# 2_Motors_V3.net
KiCad netlist of a schematic drawn in EAGLE
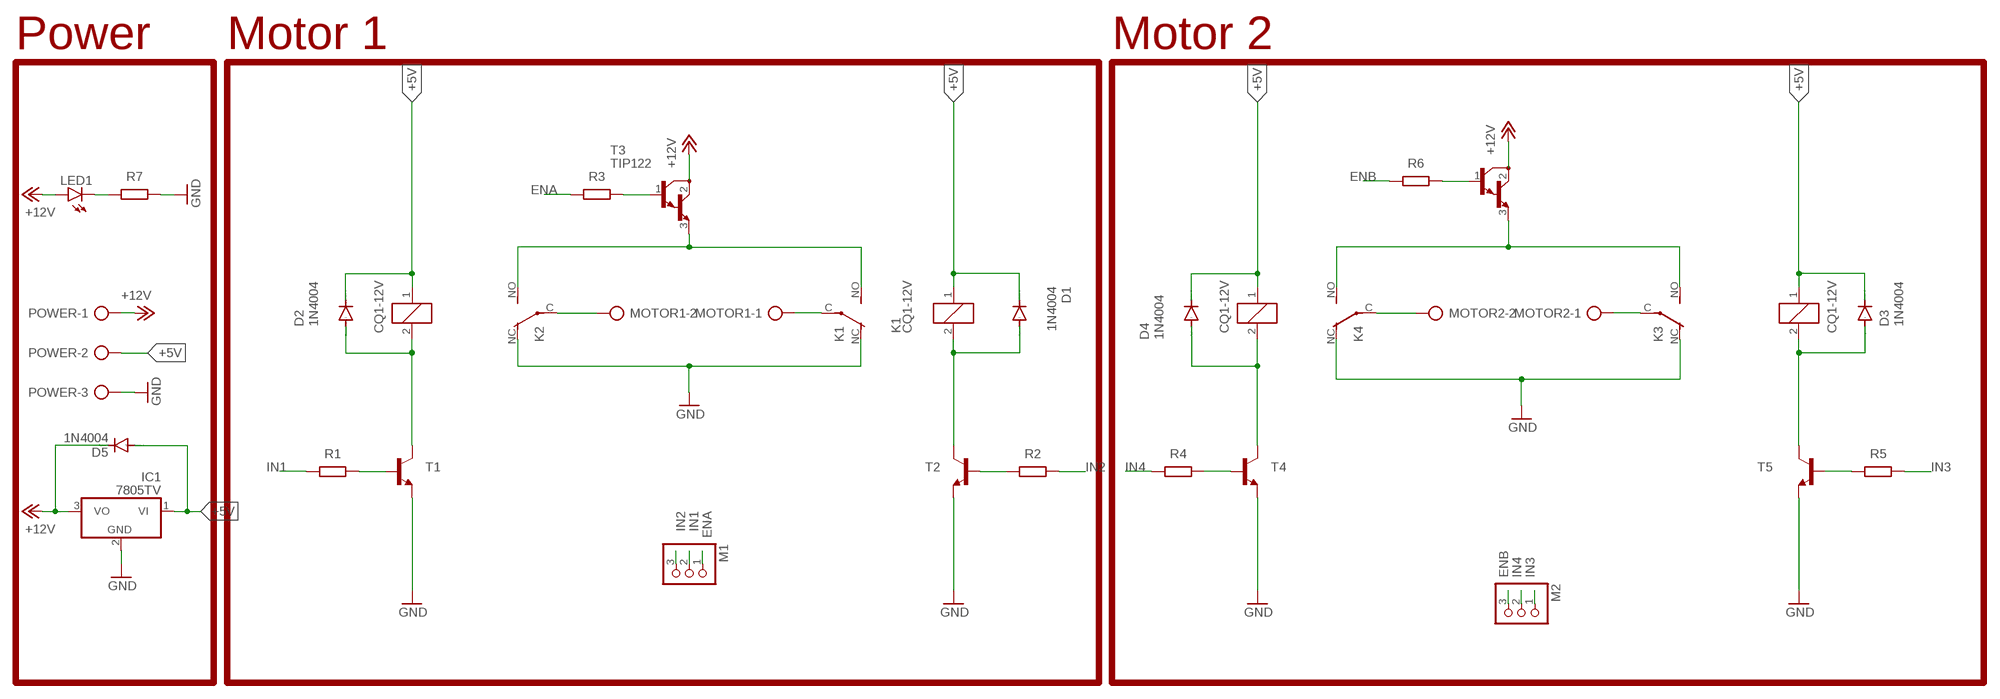
[diagram p0: schematic, sheet 1]

(export (version "E")
  (design (tool "Eeschema 10.0.6"))
  (components
    (comp (ref "D1")
      (value "1N4004")
      (footprint "eagle-import:DO41-10")
      (libsource (lib "eagle-import") (part "1N4004"))
    )
    (comp (ref "D2")
      (value "1N4004")
      (footprint "eagle-import:DO41-10")
      (libsource (lib "eagle-import") (part "1N4004"))
    )
    (comp (ref "D3")
      (value "1N4004")
      (footprint "eagle-import:DO41-10")
      (libsource (lib "eagle-import") (part "1N4004"))
    )
    (comp (ref "D4")
      (value "1N4004")
      (footprint "eagle-import:DO41-10")
      (libsource (lib "eagle-import") (part "1N4004"))
    )
    (comp (ref "D5")
      (value "1N4004")
      (footprint "eagle-import:DO41-10")
      (libsource (lib "eagle-import") (part "1N4004"))
    )
    (comp (ref "IC1")
      (value "7805TV")
      (footprint "eagle-import:TO220V")
      (libsource (lib "eagle-import") (part "78TV05"))
    )
    (comp (ref "K1")
      (value "CQ1-12V")
      (footprint "eagle-import:CQ1")
      (libsource (lib "eagle-import") (part "CQ1-12V"))
    )
    (comp (ref "K2")
      (value "CQ1-12V")
      (footprint "eagle-import:CQ1")
      (libsource (lib "eagle-import") (part "CQ1-12V"))
    )
    (comp (ref "K3")
      (value "CQ1-12V")
      (footprint "eagle-import:CQ1")
      (libsource (lib "eagle-import") (part "CQ1-12V"))
    )
    (comp (ref "K4")
      (value "CQ1-12V")
      (footprint "eagle-import:CQ1")
      (libsource (lib "eagle-import") (part "CQ1-12V"))
    )
    (comp (ref "LED1")
      (value "LED3MM")
      (footprint "eagle-import:LED3MM")
      (libsource (lib "eagle-import") (part "LED3MM"))
    )
    (comp (ref "M1")
      (value "PINHD-1X3")
      (footprint "eagle-import:1X03")
      (libsource (lib "eagle-import") (part "PINHD-1X3"))
    )
    (comp (ref "M2")
      (value "PINHD-1X3")
      (footprint "eagle-import:1X03")
      (libsource (lib "eagle-import") (part "PINHD-1X3"))
    )
    (comp (ref "MOTOR1")
      (value "AK300/2")
      (footprint "eagle-import:AK300_2")
      (libsource (lib "eagle-import") (part "AK300/2"))
    )
    (comp (ref "MOTOR2")
      (value "AK300/2")
      (footprint "eagle-import:AK300_2")
      (libsource (lib "eagle-import") (part "AK300/2"))
    )
    (comp (ref "POWER")
      (value "AK300/3")
      (footprint "eagle-import:AK300_3")
      (libsource (lib "eagle-import") (part "AK300/3"))
    )
    (comp (ref "R1")
      (value "4.7k")
      (footprint "eagle-import:0204_7")
      (libsource (lib "eagle-import") (part "R-EU_0204/7"))
    )
    (comp (ref "R2")
      (value "4.7k")
      (footprint "eagle-import:0204_7")
      (libsource (lib "eagle-import") (part "R-EU_0204/7"))
    )
    (comp (ref "R3")
      (value "4.7k")
      (footprint "eagle-import:0204_7")
      (libsource (lib "eagle-import") (part "R-EU_0204/7"))
    )
    (comp (ref "R4")
      (value "4.7k")
      (footprint "eagle-import:0204_7")
      (libsource (lib "eagle-import") (part "R-EU_0204/7"))
    )
    (comp (ref "R5")
      (value "4.7k")
      (footprint "eagle-import:0204_7")
      (libsource (lib "eagle-import") (part "R-EU_0204/7"))
    )
    (comp (ref "R6")
      (value "4.7k")
      (footprint "eagle-import:0204_7")
      (libsource (lib "eagle-import") (part "R-EU_0204/7"))
    )
    (comp (ref "R7")
      (value "330")
      (footprint "eagle-import:0204_7")
      (libsource (lib "eagle-import") (part "R-EU_0204/7"))
    )
    (comp (ref "T1")
      (value "2N2222-NPN-TO92-EBC")
      (footprint "eagle-import:TO92-EBC")
      (libsource (lib "eagle-import") (part "-NPN-TO92-EBC2N2222"))
    )
    (comp (ref "T2")
      (value "2N2222-NPN-TO92-EBC")
      (footprint "eagle-import:TO92-EBC")
      (libsource (lib "eagle-import") (part "-NPN-TO92-EBC2N2222"))
    )
    (comp (ref "T3")
      (value "TIP122")
      (footprint "eagle-import:TO220")
      (libsource (lib "eagle-import") (part "TIP122"))
    )
    (comp (ref "T4")
      (value "2N2222-NPN-TO92-EBC")
      (footprint "eagle-import:TO92-EBC")
      (libsource (lib "eagle-import") (part "-NPN-TO92-EBC2N2222"))
    )
    (comp (ref "T5")
      (value "2N2222-NPN-TO92-EBC")
      (footprint "eagle-import:TO92-EBC")
      (libsource (lib "eagle-import") (part "-NPN-TO92-EBC2N2222"))
    )
    (comp (ref "T6")
      (value "TIP122")
      (footprint "eagle-import:TO220")
      (libsource (lib "eagle-import") (part "TIP122"))
    )
  )
  (nets
    (net (code "1") (name "+5V") (class "Default")
      (node (ref "D1") (pin "C") (pinfunction "C_C") (pintype "passive"))
      (node (ref "D2") (pin "C") (pinfunction "C_C") (pintype "passive"))
      (node (ref "D3") (pin "C") (pinfunction "C_C") (pintype "passive"))
      (node (ref "D4") (pin "C") (pinfunction "C_C") (pintype "passive"))
      (node (ref "D5") (pin "A") (pinfunction "A_A") (pintype "passive"))
      (node (ref "IC1") (pin "1") (pinfunction "VI_1") (pintype "input"))
      (node (ref "K1") (pin "1") (pinfunction "1_1") (pintype "passive"))
      (node (ref "K2") (pin "1") (pinfunction "1_1") (pintype "passive"))
      (node (ref "K3") (pin "1") (pinfunction "1_1") (pintype "passive"))
      (node (ref "K4") (pin "1") (pinfunction "1_1") (pintype "passive"))
      (node (ref "POWER") (pin "2") (pinfunction "KL_2") (pintype "passive"))
    )
    (net (code "2") (name "+12V") (class "Default")
      (node (ref "D5") (pin "C") (pinfunction "C_C") (pintype "passive"))
      (node (ref "IC1") (pin "3") (pinfunction "VO_3") (pintype "passive"))
      (node (ref "LED1") (pin "A") (pinfunction "A_A") (pintype "passive"))
      (node (ref "POWER") (pin "1") (pinfunction "KL_1") (pintype "passive"))
      (node (ref "T3") (pin "2") (pinfunction "C_2") (pintype "passive"))
      (node (ref "T6") (pin "2") (pinfunction "C_2") (pintype "passive"))
    )
    (net (code "3") (name "/ENA") (class "Default")
      (node (ref "M1") (pin "1") (pinfunction "1_1") (pintype "passive"))
      (node (ref "R3") (pin "2") (pinfunction "2_2") (pintype "passive"))
    )
    (net (code "4") (name "/ENB") (class "Default")
      (node (ref "M2") (pin "3") (pinfunction "3_3") (pintype "passive"))
      (node (ref "R6") (pin "2") (pinfunction "2_2") (pintype "passive"))
    )
    (net (code "5") (name "/IN1") (class "Default")
      (node (ref "M1") (pin "2") (pinfunction "2_2") (pintype "passive"))
      (node (ref "R1") (pin "1") (pinfunction "1_1") (pintype "passive"))
    )
    (net (code "6") (name "/IN2") (class "Default")
      (node (ref "M1") (pin "3") (pinfunction "3_3") (pintype "passive"))
      (node (ref "R2") (pin "1") (pinfunction "1_1") (pintype "passive"))
    )
    (net (code "7") (name "/IN3") (class "Default")
      (node (ref "M2") (pin "1") (pinfunction "1_1") (pintype "passive"))
      (node (ref "R5") (pin "1") (pinfunction "1_1") (pintype "passive"))
    )
    (net (code "8") (name "/IN4") (class "Default")
      (node (ref "M2") (pin "2") (pinfunction "2_2") (pintype "passive"))
      (node (ref "R4") (pin "2") (pinfunction "2_2") (pintype "passive"))
    )
    (net (code "9") (name "GND") (class "Default")
      (node (ref "IC1") (pin "2") (pinfunction "GND_2") (pintype "passive"))
      (node (ref "K1") (pin "NC") (pinfunction "O_NC") (pintype "passive"))
      (node (ref "K2") (pin "NC") (pinfunction "O_NC") (pintype "passive"))
      (node (ref "K3") (pin "NC") (pinfunction "O_NC") (pintype "passive"))
      (node (ref "K4") (pin "NC") (pinfunction "O_NC") (pintype "passive"))
      (node (ref "POWER") (pin "3") (pinfunction "KL_3") (pintype "passive"))
      (node (ref "R7") (pin "2") (pinfunction "2_2") (pintype "passive"))
      (node (ref "T1") (pin "E") (pinfunction "E_E") (pintype "passive"))
      (node (ref "T2") (pin "E") (pinfunction "E_E") (pintype "passive"))
      (node (ref "T4") (pin "E") (pinfunction "E_E") (pintype "passive"))
      (node (ref "T5") (pin "E") (pinfunction "E_E") (pintype "passive"))
    )
    (net (code "10") (name "Net-(D1-PadA)") (class "Default")
      (node (ref "D1") (pin "A") (pinfunction "A_A") (pintype "passive"))
      (node (ref "K1") (pin "2") (pinfunction "2_2") (pintype "passive"))
      (node (ref "T2") (pin "C") (pinfunction "C_C") (pintype "passive"))
    )
    (net (code "11") (name "Net-(D2-PadA)") (class "Default")
      (node (ref "D2") (pin "A") (pinfunction "A_A") (pintype "passive"))
      (node (ref "K2") (pin "2") (pinfunction "2_2") (pintype "passive"))
      (node (ref "T1") (pin "C") (pinfunction "C_C") (pintype "passive"))
    )
    (net (code "12") (name "Net-(D3-PadA)") (class "Default")
      (node (ref "D3") (pin "A") (pinfunction "A_A") (pintype "passive"))
      (node (ref "K3") (pin "2") (pinfunction "2_2") (pintype "passive"))
      (node (ref "T5") (pin "C") (pinfunction "C_C") (pintype "passive"))
    )
    (net (code "13") (name "Net-(D4-PadA)") (class "Default")
      (node (ref "D4") (pin "A") (pinfunction "A_A") (pintype "passive"))
      (node (ref "K4") (pin "2") (pinfunction "2_2") (pintype "passive"))
      (node (ref "T4") (pin "C") (pinfunction "C_C") (pintype "passive"))
    )
    (net (code "14") (name "Net-(K1B-P)") (class "Default")
      (node (ref "K1") (pin "C") (pinfunction "P_C") (pintype "passive"))
      (node (ref "MOTOR1") (pin "1") (pinfunction "KL_1") (pintype "passive"))
    )
    (net (code "15") (name "Net-(K1B-S)") (class "Default")
      (node (ref "K1") (pin "NO") (pinfunction "S_NO") (pintype "passive"))
      (node (ref "K2") (pin "NO") (pinfunction "S_NO") (pintype "passive"))
      (node (ref "T3") (pin "3") (pinfunction "E_3") (pintype "passive"))
    )
    (net (code "16") (name "Net-(K2B-P)") (class "Default")
      (node (ref "K2") (pin "C") (pinfunction "P_C") (pintype "passive"))
      (node (ref "MOTOR1") (pin "2") (pinfunction "KL_2") (pintype "passive"))
    )
    (net (code "17") (name "Net-(K3B-P)") (class "Default")
      (node (ref "K3") (pin "C") (pinfunction "P_C") (pintype "passive"))
      (node (ref "MOTOR2") (pin "1") (pinfunction "KL_1") (pintype "passive"))
    )
    (net (code "18") (name "Net-(K3B-S)") (class "Default")
      (node (ref "K3") (pin "NO") (pinfunction "S_NO") (pintype "passive"))
      (node (ref "K4") (pin "NO") (pinfunction "S_NO") (pintype "passive"))
      (node (ref "T6") (pin "3") (pinfunction "E_3") (pintype "passive"))
    )
    (net (code "19") (name "Net-(K4B-P)") (class "Default")
      (node (ref "K4") (pin "C") (pinfunction "P_C") (pintype "passive"))
      (node (ref "MOTOR2") (pin "2") (pinfunction "KL_2") (pintype "passive"))
    )
    (net (code "20") (name "Net-(LED1-C)") (class "Default")
      (node (ref "LED1") (pin "K") (pinfunction "C_K") (pintype "passive"))
      (node (ref "R7") (pin "1") (pinfunction "1_1") (pintype "passive"))
    )
    (net (code "21") (name "Net-(R1-Pad2)") (class "Default")
      (node (ref "R1") (pin "2") (pinfunction "2_2") (pintype "passive"))
      (node (ref "T1") (pin "B") (pinfunction "B_B") (pintype "passive"))
    )
    (net (code "22") (name "Net-(R2-Pad2)") (class "Default")
      (node (ref "R2") (pin "2") (pinfunction "2_2") (pintype "passive"))
      (node (ref "T2") (pin "B") (pinfunction "B_B") (pintype "passive"))
    )
    (net (code "23") (name "Net-(R4-Pad1)") (class "Default")
      (node (ref "R4") (pin "1") (pinfunction "1_1") (pintype "passive"))
      (node (ref "T4") (pin "B") (pinfunction "B_B") (pintype "passive"))
    )
    (net (code "24") (name "Net-(R5-Pad2)") (class "Default")
      (node (ref "R5") (pin "2") (pinfunction "2_2") (pintype "passive"))
      (node (ref "T5") (pin "B") (pinfunction "B_B") (pintype "passive"))
    )
    (net (code "25") (name "Net-(T3-B)") (class "Default")
      (node (ref "R3") (pin "1") (pinfunction "1_1") (pintype "passive"))
      (node (ref "T3") (pin "1") (pinfunction "B_1") (pintype "passive"))
    )
    (net (code "26") (name "Net-(T6-B)") (class "Default")
      (node (ref "R6") (pin "1") (pinfunction "1_1") (pintype "passive"))
      (node (ref "T6") (pin "1") (pinfunction "B_1") (pintype "passive"))
    )
  )
)
